# Sensor_IR.net
KiCad netlist of a schematic drawn in EAGLE
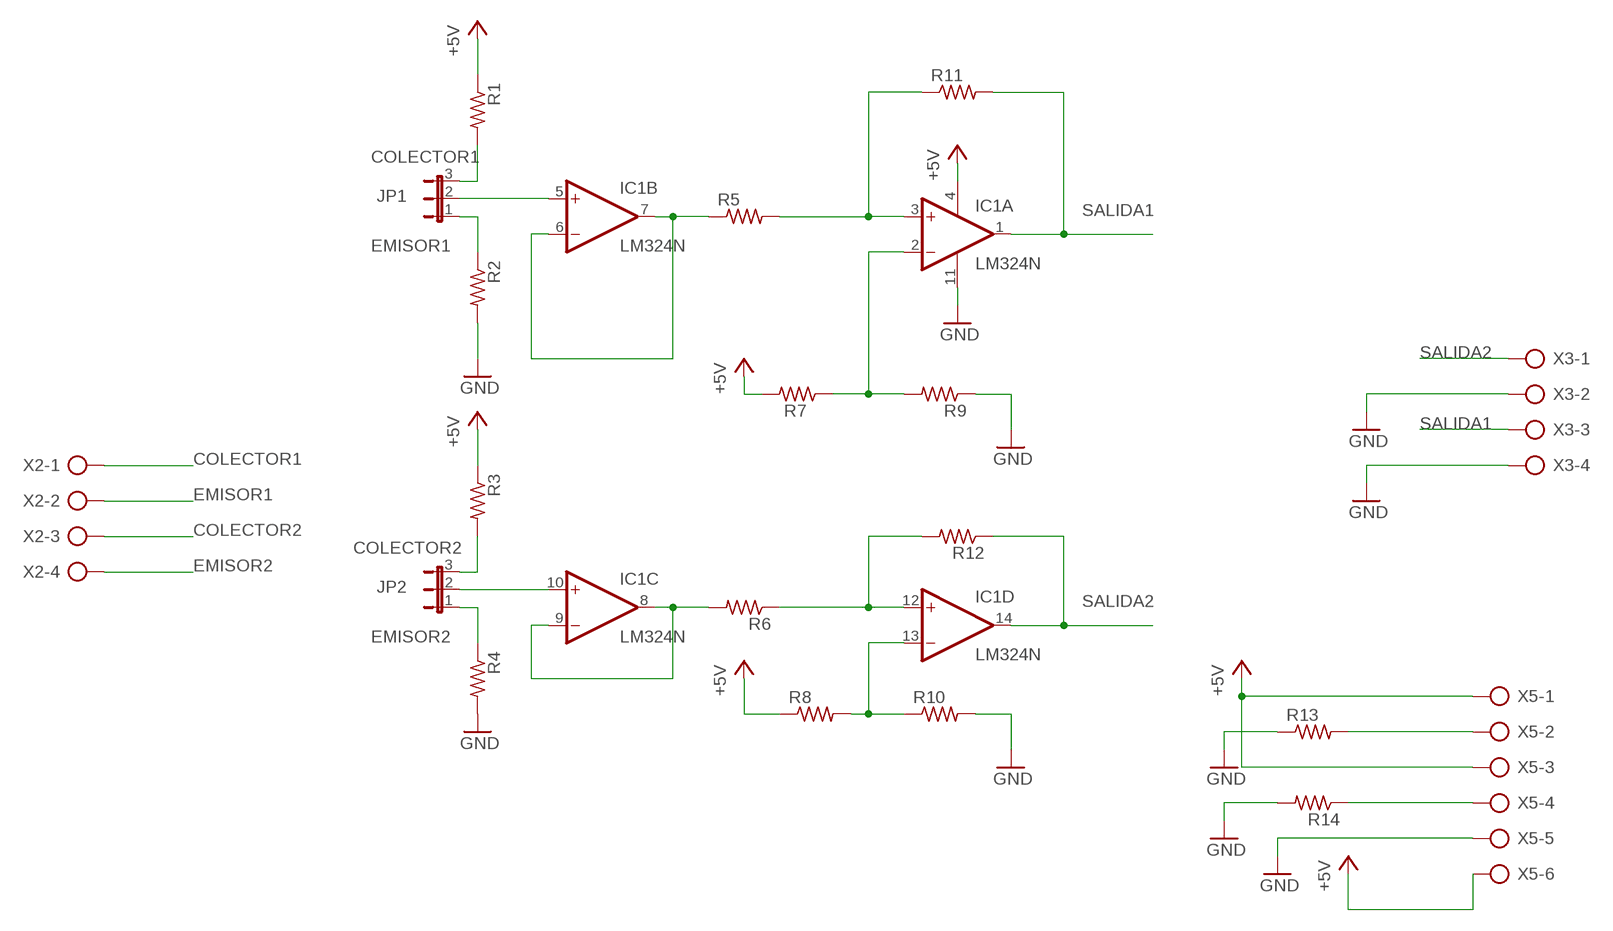
[diagram p0: schematic, sheet 1]

(export (version "E")
  (design (tool "Eeschema 10.0.6"))
  (components
    (comp (ref "IC1")
      (value "LM324N")
      (footprint "eagle-import:DIL14")
      (libsource (lib "eagle-import") (part "LM324N"))
    )
    (comp (ref "JP1")
      (value "JP2E")
      (footprint "eagle-import:JP2")
      (libsource (lib "eagle-import") (part "JP2E"))
    )
    (comp (ref "JP2")
      (value "JP2E")
      (footprint "eagle-import:JP2")
      (libsource (lib "eagle-import") (part "JP2E"))
    )
    (comp (ref "R1")
      (value "R-US_0207/10")
      (footprint "eagle-import:0207_10")
      (libsource (lib "eagle-import") (part "R-US_0207/10"))
    )
    (comp (ref "R2")
      (value "R-US_0207/10")
      (footprint "eagle-import:0207_10")
      (libsource (lib "eagle-import") (part "R-US_0207/10"))
    )
    (comp (ref "R3")
      (value "R-US_0207/10")
      (footprint "eagle-import:0207_10")
      (libsource (lib "eagle-import") (part "R-US_0207/10"))
    )
    (comp (ref "R4")
      (value "R-US_0207/10")
      (footprint "eagle-import:0207_10")
      (libsource (lib "eagle-import") (part "R-US_0207/10"))
    )
    (comp (ref "R5")
      (value "R-US_0207/10")
      (footprint "eagle-import:0207_10")
      (libsource (lib "eagle-import") (part "R-US_0207/10"))
    )
    (comp (ref "R6")
      (value "R-US_0207/10")
      (footprint "eagle-import:0207_10")
      (libsource (lib "eagle-import") (part "R-US_0207/10"))
    )
    (comp (ref "R7")
      (value "R-US_0207/10")
      (footprint "eagle-import:0207_10")
      (libsource (lib "eagle-import") (part "R-US_0207/10"))
    )
    (comp (ref "R8")
      (value "R-US_0207/10")
      (footprint "eagle-import:0207_10")
      (libsource (lib "eagle-import") (part "R-US_0207/10"))
    )
    (comp (ref "R9")
      (value "R-US_0207/10")
      (footprint "eagle-import:0207_10")
      (libsource (lib "eagle-import") (part "R-US_0207/10"))
    )
    (comp (ref "R10")
      (value "R-US_0207/10")
      (footprint "eagle-import:0207_10")
      (libsource (lib "eagle-import") (part "R-US_0207/10"))
    )
    (comp (ref "R11")
      (value "R-US_0207/10")
      (footprint "eagle-import:0207_10")
      (libsource (lib "eagle-import") (part "R-US_0207/10"))
    )
    (comp (ref "R12")
      (value "R-US_0207/10")
      (footprint "eagle-import:0207_10")
      (libsource (lib "eagle-import") (part "R-US_0207/10"))
    )
    (comp (ref "R13")
      (value "R-US_0207/10")
      (footprint "eagle-import:0207_10")
      (libsource (lib "eagle-import") (part "R-US_0207/10"))
    )
    (comp (ref "R14")
      (value "R-US_0207/10")
      (footprint "eagle-import:0207_10")
      (libsource (lib "eagle-import") (part "R-US_0207/10"))
    )
    (comp (ref "X2")
      (value "AK500/4-H")
      (footprint "eagle-import:AK500_4-H")
      (libsource (lib "eagle-import") (part "AK500/4-H"))
    )
    (comp (ref "X3")
      (value "AK500/4-H")
      (footprint "eagle-import:AK500_4-H")
      (libsource (lib "eagle-import") (part "AK500/4-H"))
    )
    (comp (ref "X5")
      (value "AK500/6-H")
      (footprint "eagle-import:AK500_6-H")
      (libsource (lib "eagle-import") (part "AK500/6-H"))
    )
  )
  (nets
    (net (code "1") (name "+5V") (class "Default")
      (node (ref "IC1") (pin "4") (pinfunction "V+_4") (pintype "power_in"))
      (node (ref "R1") (pin "1") (pinfunction "1_1") (pintype "passive"))
      (node (ref "R3") (pin "1") (pinfunction "1_1") (pintype "passive"))
      (node (ref "R7") (pin "2") (pinfunction "2_2") (pintype "passive"))
      (node (ref "R8") (pin "1") (pinfunction "1_1") (pintype "passive"))
      (node (ref "X5") (pin "1") (pinfunction "KL_1") (pintype "passive"))
      (node (ref "X5") (pin "3") (pinfunction "KL_3") (pintype "passive"))
      (node (ref "X5") (pin "6") (pinfunction "KL_6") (pintype "passive"))
    )
    (net (code "2") (name "/COLECTOR1") (class "Default")
      (node (ref "JP1") (pin "3") (pinfunction "3_3") (pintype "passive"))
      (node (ref "R1") (pin "2") (pinfunction "2_2") (pintype "passive"))
      (node (ref "X2") (pin "1") (pinfunction "KL_1") (pintype "passive"))
    )
    (net (code "3") (name "/COLECTOR2") (class "Default")
      (node (ref "JP2") (pin "3") (pinfunction "3_3") (pintype "passive"))
      (node (ref "R3") (pin "2") (pinfunction "2_2") (pintype "passive"))
      (node (ref "X2") (pin "3") (pinfunction "KL_3") (pintype "passive"))
    )
    (net (code "4") (name "/EMISOR1") (class "Default")
      (node (ref "JP1") (pin "1") (pinfunction "1_1") (pintype "passive"))
      (node (ref "R2") (pin "1") (pinfunction "1_1") (pintype "passive"))
      (node (ref "X2") (pin "2") (pinfunction "KL_2") (pintype "passive"))
    )
    (net (code "5") (name "/EMISOR2") (class "Default")
      (node (ref "JP2") (pin "1") (pinfunction "1_1") (pintype "passive"))
      (node (ref "R4") (pin "1") (pinfunction "1_1") (pintype "passive"))
      (node (ref "X2") (pin "4") (pinfunction "KL_4") (pintype "passive"))
    )
    (net (code "6") (name "/SALIDA1") (class "Default")
      (node (ref "IC1") (pin "1") (pinfunction "OUT_1") (pintype "output"))
      (node (ref "R11") (pin "2") (pinfunction "2_2") (pintype "passive"))
      (node (ref "X3") (pin "3") (pinfunction "KL_3") (pintype "passive"))
    )
    (net (code "7") (name "/SALIDA2") (class "Default")
      (node (ref "IC1") (pin "14") (pinfunction "OUT_14") (pintype "output"))
      (node (ref "R12") (pin "1") (pinfunction "1_1") (pintype "passive"))
      (node (ref "X3") (pin "1") (pinfunction "KL_1") (pintype "passive"))
    )
    (net (code "8") (name "GND") (class "Default")
      (node (ref "IC1") (pin "11") (pinfunction "V-_11") (pintype "power_in"))
      (node (ref "R10") (pin "2") (pinfunction "2_2") (pintype "passive"))
      (node (ref "R13") (pin "1") (pinfunction "1_1") (pintype "passive"))
      (node (ref "R14") (pin "2") (pinfunction "2_2") (pintype "passive"))
      (node (ref "R2") (pin "2") (pinfunction "2_2") (pintype "passive"))
      (node (ref "R4") (pin "2") (pinfunction "2_2") (pintype "passive"))
      (node (ref "R9") (pin "1") (pinfunction "1_1") (pintype "passive"))
      (node (ref "X3") (pin "2") (pinfunction "KL_2") (pintype "passive"))
      (node (ref "X3") (pin "4") (pinfunction "KL_4") (pintype "passive"))
      (node (ref "X5") (pin "5") (pinfunction "KL_5") (pintype "passive"))
    )
    (net (code "9") (name "Net-(IC1A-+IN)") (class "Default")
      (node (ref "IC1") (pin "3") (pinfunction "+IN_3") (pintype "input"))
      (node (ref "R11") (pin "1") (pinfunction "1_1") (pintype "passive"))
      (node (ref "R5") (pin "2") (pinfunction "2_2") (pintype "passive"))
    )
    (net (code "10") (name "Net-(IC1A--IN)") (class "Default")
      (node (ref "IC1") (pin "2") (pinfunction "-IN_2") (pintype "input"))
      (node (ref "R7") (pin "1") (pinfunction "1_1") (pintype "passive"))
      (node (ref "R9") (pin "2") (pinfunction "2_2") (pintype "passive"))
    )
    (net (code "11") (name "Net-(IC1B-+IN)") (class "Default")
      (node (ref "IC1") (pin "5") (pinfunction "+IN_5") (pintype "input"))
      (node (ref "JP1") (pin "2") (pinfunction "2_2") (pintype "passive"))
    )
    (net (code "12") (name "Net-(IC1B--IN)") (class "Default")
      (node (ref "IC1") (pin "6") (pinfunction "-IN_6") (pintype "input"))
      (node (ref "IC1") (pin "7") (pinfunction "OUT_7") (pintype "output"))
      (node (ref "R5") (pin "1") (pinfunction "1_1") (pintype "passive"))
    )
    (net (code "13") (name "Net-(IC1C-+IN)") (class "Default")
      (node (ref "IC1") (pin "10") (pinfunction "+IN_10") (pintype "input"))
      (node (ref "JP2") (pin "2") (pinfunction "2_2") (pintype "passive"))
    )
    (net (code "14") (name "Net-(IC1C--IN)") (class "Default")
      (node (ref "IC1") (pin "8") (pinfunction "OUT_8") (pintype "output"))
      (node (ref "IC1") (pin "9") (pinfunction "-IN_9") (pintype "input"))
      (node (ref "R6") (pin "2") (pinfunction "2_2") (pintype "passive"))
    )
    (net (code "15") (name "Net-(IC1D-+IN)") (class "Default")
      (node (ref "IC1") (pin "12") (pinfunction "+IN_12") (pintype "input"))
      (node (ref "R12") (pin "2") (pinfunction "2_2") (pintype "passive"))
      (node (ref "R6") (pin "1") (pinfunction "1_1") (pintype "passive"))
    )
    (net (code "16") (name "Net-(IC1D--IN)") (class "Default")
      (node (ref "IC1") (pin "13") (pinfunction "-IN_13") (pintype "input"))
      (node (ref "R10") (pin "1") (pinfunction "1_1") (pintype "passive"))
      (node (ref "R8") (pin "2") (pinfunction "2_2") (pintype "passive"))
    )
    (net (code "17") (name "Net-(X5B-KL)") (class "Default")
      (node (ref "R13") (pin "2") (pinfunction "2_2") (pintype "passive"))
      (node (ref "X5") (pin "2") (pinfunction "KL_2") (pintype "passive"))
    )
    (net (code "18") (name "Net-(X5D-KL)") (class "Default")
      (node (ref "R14") (pin "1") (pinfunction "1_1") (pintype "passive"))
      (node (ref "X5") (pin "4") (pinfunction "KL_4") (pintype "passive"))
    )
  )
)
